# io_board.net
KiCad netlist of a schematic drawn in EAGLE
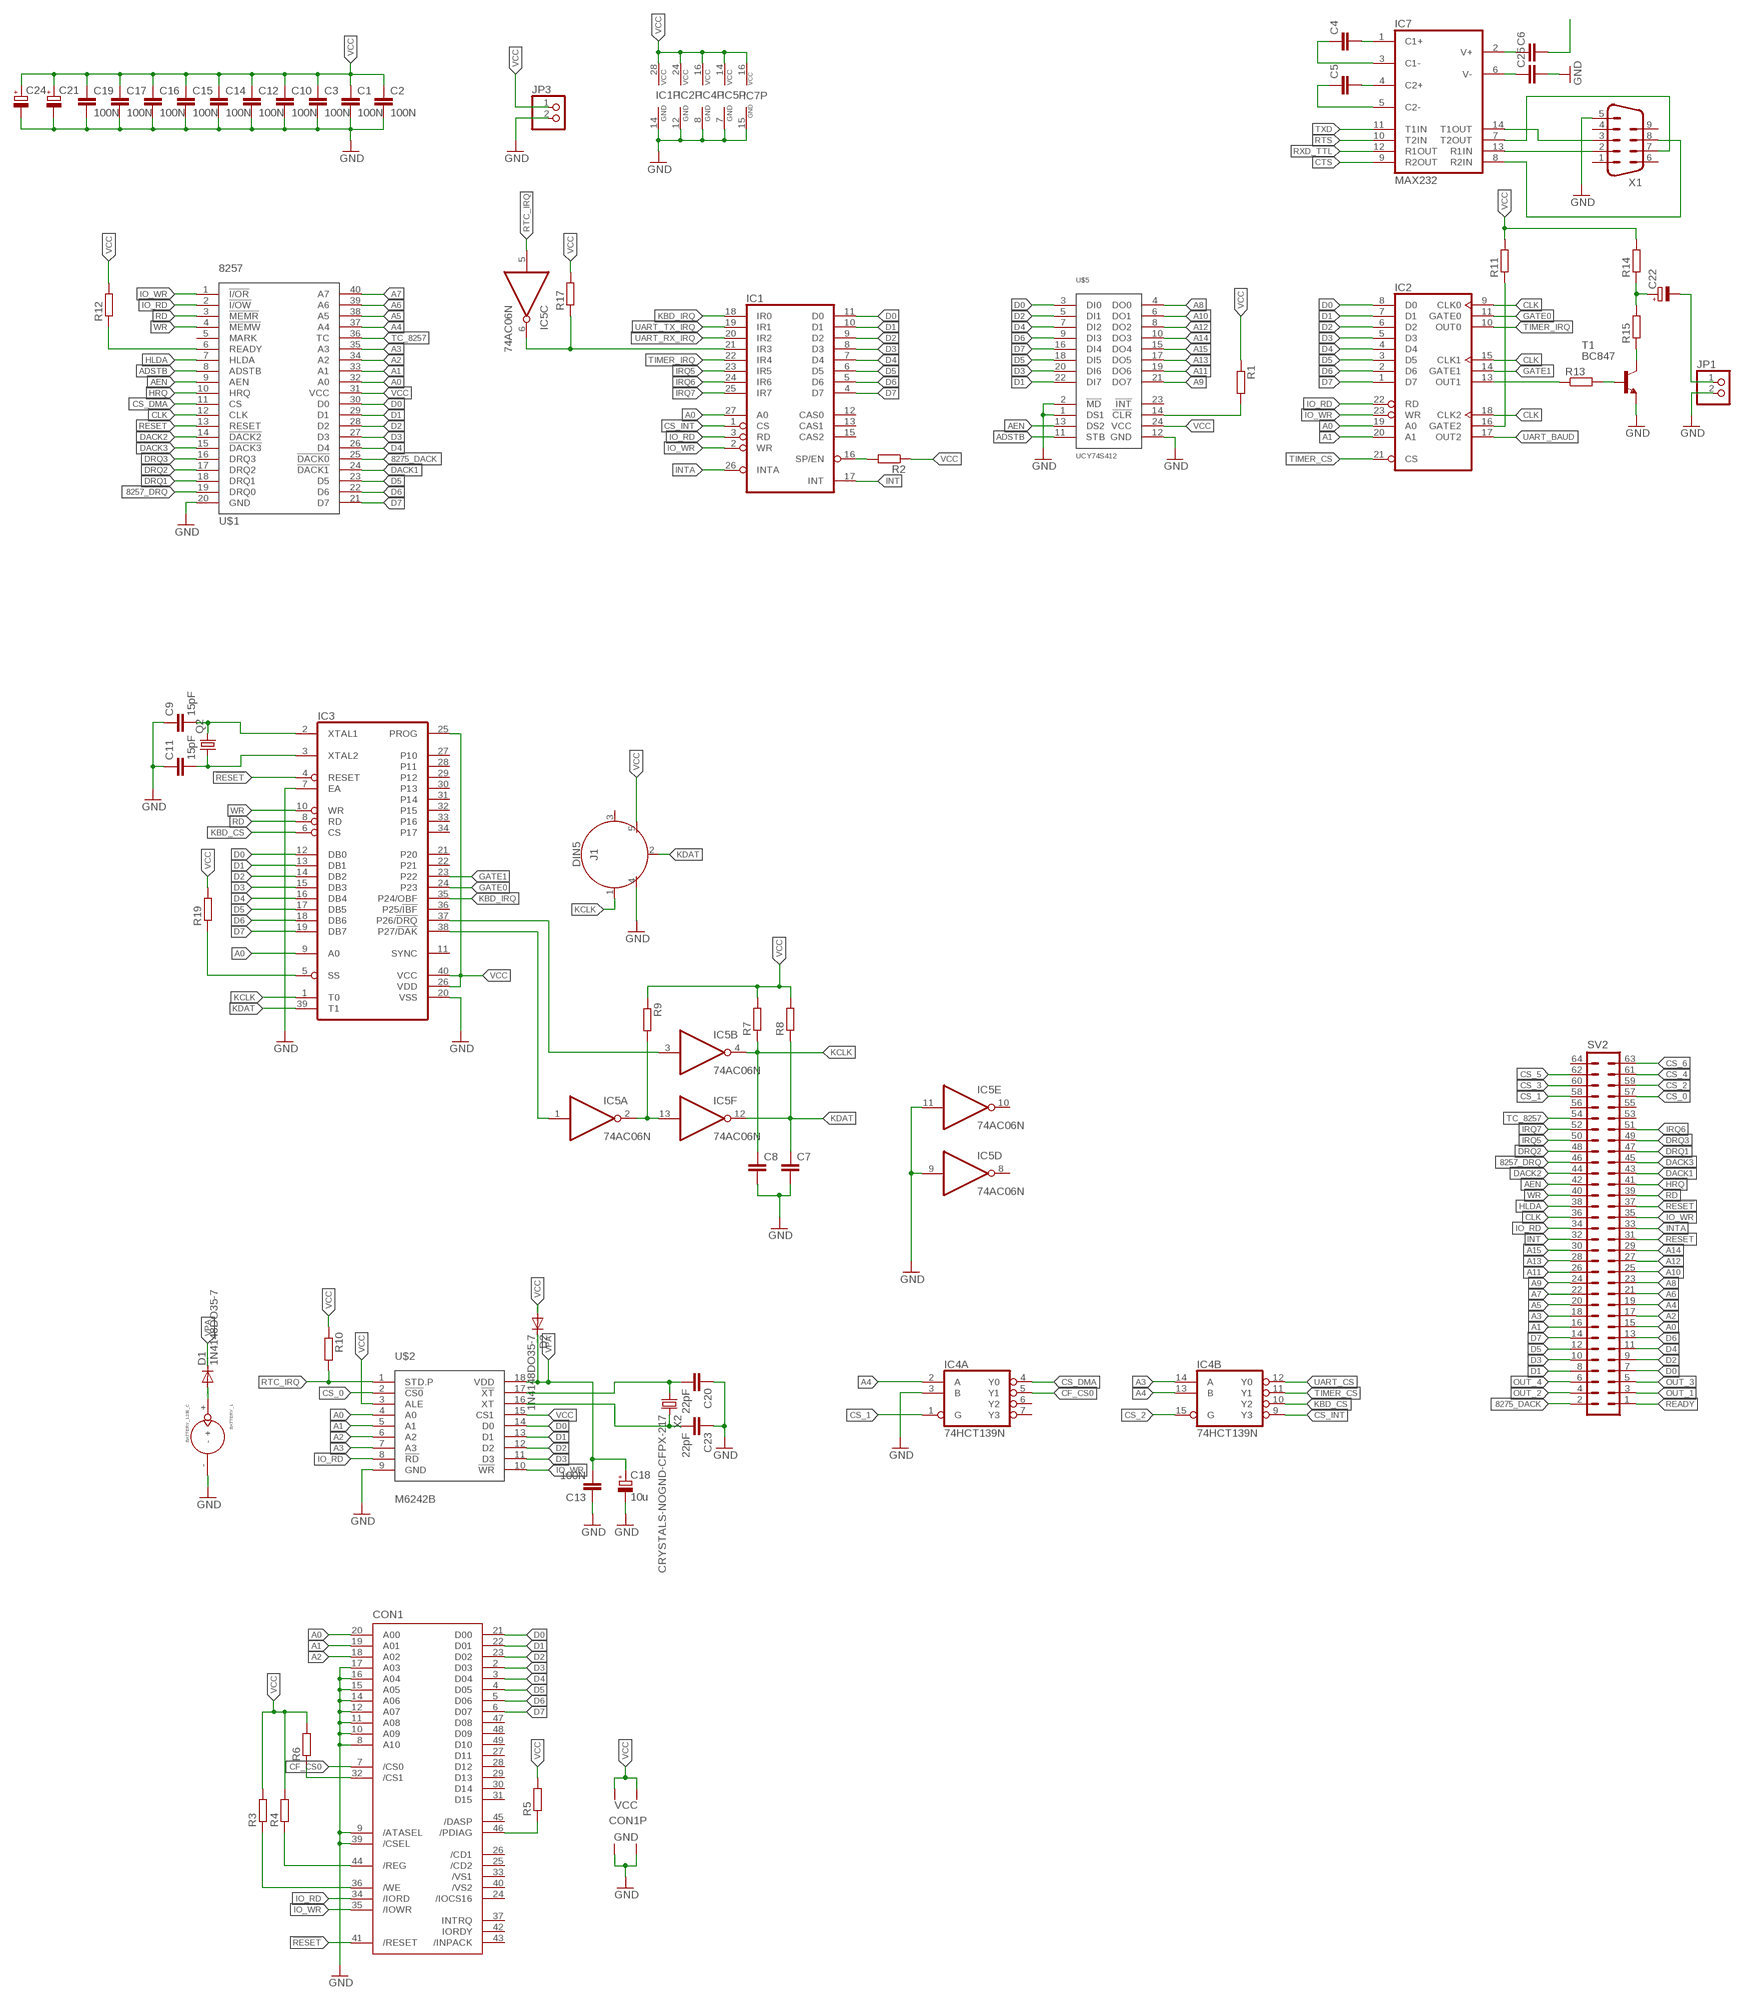
[diagram p0: schematic, sheet 1, part 1 of 2]
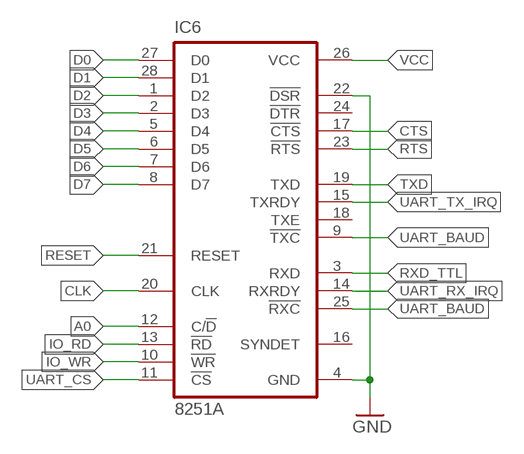
[diagram p1: schematic, sheet 1, part 2 of 2]

(export (version "E")
  (design (tool "Eeschema 10.0.6"))
  (components
    (comp (ref "BATTERY_1")
      (value "BATTERY_1236_C")
      (footprint "eagle-import:BATTERY_1236_C")
      (libsource (lib "eagle-import") (part "BATTERY_1236_C"))
    )
    (comp (ref "C1")
      (value "100N")
      (footprint "eagle-import:C0603")
      (libsource (lib "eagle-import") (part "C-EUC0603"))
    )
    (comp (ref "C2")
      (value "100N")
      (footprint "eagle-import:C1206")
      (libsource (lib "eagle-import") (part "C-EUC1206"))
    )
    (comp (ref "C3")
      (value "100N")
      (footprint "eagle-import:C0603")
      (libsource (lib "eagle-import") (part "C-EUC0603"))
    )
    (comp (ref "C4")
      (value "C-EUC0603")
      (footprint "eagle-import:C0603")
      (libsource (lib "eagle-import") (part "C-EUC0603"))
    )
    (comp (ref "C5")
      (value "C-EUC0603")
      (footprint "eagle-import:C0603")
      (libsource (lib "eagle-import") (part "C-EUC0603"))
    )
    (comp (ref "C6")
      (value "C-EUC0603")
      (footprint "eagle-import:C0603")
      (libsource (lib "eagle-import") (part "C-EUC0603"))
    )
    (comp (ref "C7")
      (value "C-EUC0603")
      (footprint "eagle-import:C0603")
      (libsource (lib "eagle-import") (part "C-EUC0603"))
    )
    (comp (ref "C8")
      (value "C-EUC0603")
      (footprint "eagle-import:C0603")
      (libsource (lib "eagle-import") (part "C-EUC0603"))
    )
    (comp (ref "C9")
      (value "15pF")
      (footprint "eagle-import:C0603")
      (libsource (lib "eagle-import") (part "C-EUC0603"))
    )
    (comp (ref "C10")
      (value "100N")
      (footprint "eagle-import:C0603")
      (libsource (lib "eagle-import") (part "C-EUC0603"))
    )
    (comp (ref "C11")
      (value "15pF")
      (footprint "eagle-import:C0603")
      (libsource (lib "eagle-import") (part "C-EUC0603"))
    )
    (comp (ref "C12")
      (value "100N")
      (footprint "eagle-import:C0603")
      (libsource (lib "eagle-import") (part "C-EUC0603"))
    )
    (comp (ref "C13")
      (value "100N")
      (footprint "eagle-import:C0603")
      (libsource (lib "eagle-import") (part "C-EUC0603"))
    )
    (comp (ref "C14")
      (value "100N")
      (footprint "eagle-import:C0603")
      (libsource (lib "eagle-import") (part "C-EUC0603"))
    )
    (comp (ref "C15")
      (value "100N")
      (footprint "eagle-import:C0603")
      (libsource (lib "eagle-import") (part "C-EUC0603"))
    )
    (comp (ref "C16")
      (value "100N")
      (footprint "eagle-import:C0603")
      (libsource (lib "eagle-import") (part "C-EUC0603"))
    )
    (comp (ref "C17")
      (value "100N")
      (footprint "eagle-import:C0603")
      (libsource (lib "eagle-import") (part "C-EUC0603"))
    )
    (comp (ref "C18")
      (value "10u")
      (footprint "eagle-import:SMC_B")
      (libsource (lib "eagle-import") (part "CPOL-EUSMCB"))
    )
    (comp (ref "C19")
      (value "100N")
      (footprint "eagle-import:C0603")
      (libsource (lib "eagle-import") (part "C-EUC0603"))
    )
    (comp (ref "C20")
      (value "22pF")
      (footprint "eagle-import:C0603")
      (libsource (lib "eagle-import") (part "C-EUC0603"))
    )
    (comp (ref "C21")
      (value "CPOL-EUE3.5-8")
      (footprint "eagle-import:E3,5-8")
      (libsource (lib "eagle-import") (part "CPOL-EUE3.5-8"))
    )
    (comp (ref "C22")
      (value "CPOL-EUE2-4")
      (footprint "eagle-import:E2-4")
      (libsource (lib "eagle-import") (part "CPOL-EUE2-4"))
    )
    (comp (ref "C23")
      (value "22pF")
      (footprint "eagle-import:C0603")
      (libsource (lib "eagle-import") (part "C-EUC0603"))
    )
    (comp (ref "C24")
      (value "CPOL-EUSMCB")
      (footprint "eagle-import:SMC_B")
      (libsource (lib "eagle-import") (part "CPOL-EUSMCB"))
    )
    (comp (ref "C25")
      (value "C-EUC0603")
      (footprint "eagle-import:C0603")
      (libsource (lib "eagle-import") (part "C-EUC0603"))
    )
    (comp (ref "CON1")
      (value "CF-CARD-IDE_MODE")
      (footprint "eagle-import:MI20-50PD-SF")
      (libsource (lib "eagle-import") (part "CF-CARD-IDE_MODE"))
    )
    (comp (ref "D1")
      (value "1N4148DO35-7")
      (footprint "eagle-import:DO35-7")
      (libsource (lib "eagle-import") (part "1N4148DO35-7"))
    )
    (comp (ref "D2")
      (value "1N4148DO35-7")
      (footprint "eagle-import:DO35-7")
      (libsource (lib "eagle-import") (part "1N4148DO35-7"))
    )
    (comp (ref "IC1")
      (value "8259A")
      (footprint "eagle-import:DIL28-6")
      (libsource (lib "eagle-import") (part "8259A"))
    )
    (comp (ref "IC2")
      (value "8253")
      (footprint "eagle-import:DIL24-6")
      (libsource (lib "eagle-import") (part "8253"))
    )
    (comp (ref "IC3")
      (value "UPI-8042AH")
      (footprint "eagle-import:DIL40")
      (libsource (lib "eagle-import") (part "UPI-8042AH"))
    )
    (comp (ref "IC4")
      (value "74HCT139N")
      (footprint "eagle-import:DIL16")
      (libsource (lib "eagle-import") (part "74139NHCT"))
    )
    (comp (ref "IC5")
      (value "74AC06N")
      (footprint "eagle-import:DIL14")
      (libsource (lib "eagle-import") (part "7406NAC"))
    )
    (comp (ref "IC6")
      (value "8251A")
      (footprint "eagle-import:DIL28-6")
      (libsource (lib "eagle-import") (part "8251A"))
    )
    (comp (ref "IC7")
      (value "MAX232")
      (footprint "eagle-import:DIL16")
      (fields (field (name "MF") "MAXIM") (field (name "MPN") "MAX232ACPE+"))
      (libsource (lib "eagle-import") (part "MAX232"))
    )
    (comp (ref "J1")
      (value "DIN5")
      (footprint "eagle-import:DIN5-RA-PTH")
      (libsource (lib "eagle-import") (part "DIN5"))
    )
    (comp (ref "JP1")
      (value "PINHD-1X2")
      (footprint "eagle-import:1X02")
      (libsource (lib "eagle-import") (part "PINHD-1X2"))
    )
    (comp (ref "JP3")
      (value "PINHD-1X2/90")
      (footprint "eagle-import:1X02_90")
      (libsource (lib "eagle-import") (part "PINHD-1X2/90"))
    )
    (comp (ref "Q2")
      (value "CRYSTALHC49S")
      (footprint "eagle-import:HC49_S")
      (libsource (lib "eagle-import") (part "CRYSTALHC49S"))
    )
    (comp (ref "R1")
      (value "R-EU_R0603")
      (footprint "eagle-import:R0603")
      (libsource (lib "eagle-import") (part "R-EU_R0603"))
    )
    (comp (ref "R2")
      (value "R-EU_R0603")
      (footprint "eagle-import:R0603")
      (libsource (lib "eagle-import") (part "R-EU_R0603"))
    )
    (comp (ref "R3")
      (value "R-EU_R0603")
      (footprint "eagle-import:R0603")
      (libsource (lib "eagle-import") (part "R-EU_R0603"))
    )
    (comp (ref "R4")
      (value "R-EU_0204/7")
      (footprint "eagle-import:0204_7")
      (libsource (lib "eagle-import") (part "R-EU_0204/7"))
    )
    (comp (ref "R5")
      (value "R-EU_R0603")
      (footprint "eagle-import:R0603")
      (libsource (lib "eagle-import") (part "R-EU_R0603"))
    )
    (comp (ref "R6")
      (value "R-EU_R0603")
      (footprint "eagle-import:R0603")
      (libsource (lib "eagle-import") (part "R-EU_R0603"))
    )
    (comp (ref "R7")
      (value "R-EU_0204/5")
      (footprint "eagle-import:0204_5")
      (libsource (lib "eagle-import") (part "R-EU_0204/5"))
    )
    (comp (ref "R8")
      (value "R-EU_M0805")
      (footprint "eagle-import:M0805")
      (libsource (lib "eagle-import") (part "R-EU_M0805"))
    )
    (comp (ref "R9")
      (value "R-EU_R0603")
      (footprint "eagle-import:R0603")
      (libsource (lib "eagle-import") (part "R-EU_R0603"))
    )
    (comp (ref "R10")
      (value "R-EU_R0603")
      (footprint "eagle-import:R0603")
      (libsource (lib "eagle-import") (part "R-EU_R0603"))
    )
    (comp (ref "R11")
      (value "R-EU_R0603")
      (footprint "eagle-import:R0603")
      (libsource (lib "eagle-import") (part "R-EU_R0603"))
    )
    (comp (ref "R12")
      (value "R-EU_R0603")
      (footprint "eagle-import:R0603")
      (libsource (lib "eagle-import") (part "R-EU_R0603"))
    )
    (comp (ref "R13")
      (value "R-EU_R0603")
      (footprint "eagle-import:R0603")
      (libsource (lib "eagle-import") (part "R-EU_R0603"))
    )
    (comp (ref "R14")
      (value "R-EU_0204/5")
      (footprint "eagle-import:0204_5")
      (libsource (lib "eagle-import") (part "R-EU_0204/5"))
    )
    (comp (ref "R15")
      (value "R-EU_R0603")
      (footprint "eagle-import:R0603")
      (libsource (lib "eagle-import") (part "R-EU_R0603"))
    )
    (comp (ref "R17")
      (value "R-EU_0204/7")
      (footprint "eagle-import:0204_7")
      (libsource (lib "eagle-import") (part "R-EU_0204/7"))
    )
    (comp (ref "R19")
      (value "R-EU_0204/5")
      (footprint "eagle-import:0204_5")
      (libsource (lib "eagle-import") (part "R-EU_0204/5"))
    )
    (comp (ref "SV2")
      (value "ML64L")
      (footprint "eagle-import:ML64L")
      (libsource (lib "eagle-import") (part "ML64L"))
    )
    (comp (ref "T1")
      (value "BC847")
      (footprint "eagle-import:SOT23")
      (libsource (lib "eagle-import") (part "BC847"))
    )
    (comp (ref "U$1")
      (value "8257")
      (footprint "eagle-import:DIL40")
      (libsource (lib "eagle-import") (part "8257"))
    )
    (comp (ref "U$2")
      (value "M6242B")
      (footprint "eagle-import:DIL18")
      (libsource (lib "eagle-import") (part "M6242B"))
    )
    (comp (ref "U$5")
      (value "UCY74S412")
      (footprint "eagle-import:DIL24-6")
      (libsource (lib "eagle-import") (part "UCY74S412"))
    )
    (comp (ref "X1")
      (value "M09HP")
      (footprint "eagle-import:M09HP")
      (libsource (lib "eagle-import") (part "M09HP"))
    )
    (comp (ref "X2")
      (value "CRYSTALS-NOGND-CFPX-217")
      (footprint "eagle-import:3.2X1.5-2-PAD")
      (libsource (lib "eagle-import") (part "CRYSTALS-NOGND-CFPX-217"))
    )
  )
  (nets
    (net (code "1") (name "/~{RESET}") (class "Default")
      (node (ref "CON1") (pin "41") (pinfunction "/RESET_41") (pintype "input"))
      (node (ref "IC3") (pin "4") (pinfunction "RESET_4") (pintype "input"))
      (node (ref "SV2") (pin "37") (pinfunction "37_37") (pintype "passive"))
    )
    (net (code "2") (name "8257_DRQ") (class "Default")
      (node (ref "SV2") (pin "46") (pinfunction "46_46") (pintype "passive"))
      (node (ref "U$1") (pin "19") (pinfunction "DRQ0_19") (pintype "bidirectional"))
    )
    (net (code "3") (name "8275_DACK") (class "Default")
      (node (ref "SV2") (pin "2") (pinfunction "2_2") (pintype "passive"))
      (node (ref "U$1") (pin "25") (pinfunction "~{DACK0}_25") (pintype "bidirectional"))
    )
    (net (code "4") (name "A0") (class "Default")
      (node (ref "CON1") (pin "20") (pinfunction "A00_20") (pintype "input"))
      (node (ref "IC1") (pin "27") (pinfunction "A0_27") (pintype "input"))
      (node (ref "IC2") (pin "19") (pinfunction "A0_19") (pintype "input"))
      (node (ref "IC3") (pin "9") (pinfunction "A0_9") (pintype "input"))
      (node (ref "IC6") (pin "12") (pinfunction "C/~{D}_12") (pintype "input"))
      (node (ref "SV2") (pin "15") (pinfunction "15_15") (pintype "passive"))
      (node (ref "U$1") (pin "32") (pinfunction "A0_32") (pintype "bidirectional"))
      (node (ref "U$2") (pin "4") (pinfunction "A0_4") (pintype "bidirectional"))
    )
    (net (code "5") (name "A1") (class "Default")
      (node (ref "CON1") (pin "19") (pinfunction "A01_19") (pintype "input"))
      (node (ref "IC2") (pin "20") (pinfunction "A1_20") (pintype "input"))
      (node (ref "SV2") (pin "16") (pinfunction "16_16") (pintype "passive"))
      (node (ref "U$1") (pin "33") (pinfunction "A1_33") (pintype "bidirectional"))
      (node (ref "U$2") (pin "5") (pinfunction "A1_5") (pintype "bidirectional"))
    )
    (net (code "6") (name "A2") (class "Default")
      (node (ref "CON1") (pin "18") (pinfunction "A02_18") (pintype "input"))
      (node (ref "SV2") (pin "17") (pinfunction "17_17") (pintype "passive"))
      (node (ref "U$1") (pin "34") (pinfunction "A2_34") (pintype "bidirectional"))
      (node (ref "U$2") (pin "6") (pinfunction "A2_6") (pintype "bidirectional"))
    )
    (net (code "7") (name "A3") (class "Default")
      (node (ref "IC4") (pin "14") (pinfunction "A_14") (pintype "input"))
      (node (ref "SV2") (pin "18") (pinfunction "18_18") (pintype "passive"))
      (node (ref "U$1") (pin "35") (pinfunction "A3_35") (pintype "bidirectional"))
      (node (ref "U$2") (pin "7") (pinfunction "A3_7") (pintype "bidirectional"))
    )
    (net (code "8") (name "A4") (class "Default")
      (node (ref "IC4") (pin "13") (pinfunction "B_13") (pintype "input"))
      (node (ref "IC4") (pin "2") (pinfunction "A_2") (pintype "input"))
      (node (ref "SV2") (pin "19") (pinfunction "19_19") (pintype "passive"))
      (node (ref "U$1") (pin "37") (pinfunction "A4_37") (pintype "bidirectional"))
    )
    (net (code "9") (name "A5") (class "Default")
      (node (ref "SV2") (pin "20") (pinfunction "20_20") (pintype "passive"))
      (node (ref "U$1") (pin "38") (pinfunction "A5_38") (pintype "bidirectional"))
    )
    (net (code "10") (name "A6") (class "Default")
      (node (ref "SV2") (pin "21") (pinfunction "21_21") (pintype "passive"))
      (node (ref "U$1") (pin "39") (pinfunction "A6_39") (pintype "bidirectional"))
    )
    (net (code "11") (name "A7") (class "Default")
      (node (ref "SV2") (pin "22") (pinfunction "22_22") (pintype "passive"))
      (node (ref "U$1") (pin "40") (pinfunction "A7_40") (pintype "bidirectional"))
    )
    (net (code "12") (name "A8") (class "Default")
      (node (ref "SV2") (pin "23") (pinfunction "23_23") (pintype "passive"))
      (node (ref "U$5") (pin "4") (pinfunction "DO0_4") (pintype "bidirectional"))
    )
    (net (code "13") (name "A9") (class "Default")
      (node (ref "SV2") (pin "24") (pinfunction "24_24") (pintype "passive"))
      (node (ref "U$5") (pin "21") (pinfunction "DO7_21") (pintype "bidirectional"))
    )
    (net (code "14") (name "A10") (class "Default")
      (node (ref "SV2") (pin "25") (pinfunction "25_25") (pintype "passive"))
      (node (ref "U$5") (pin "6") (pinfunction "DO1_6") (pintype "bidirectional"))
    )
    (net (code "15") (name "A11") (class "Default")
      (node (ref "SV2") (pin "26") (pinfunction "26_26") (pintype "passive"))
      (node (ref "U$5") (pin "19") (pinfunction "DO6_19") (pintype "bidirectional"))
    )
    (net (code "16") (name "A12") (class "Default")
      (node (ref "SV2") (pin "27") (pinfunction "27_27") (pintype "passive"))
      (node (ref "U$5") (pin "8") (pinfunction "DO2_8") (pintype "bidirectional"))
    )
    (net (code "17") (name "A13") (class "Default")
      (node (ref "SV2") (pin "28") (pinfunction "28_28") (pintype "passive"))
      (node (ref "U$5") (pin "17") (pinfunction "DO5_17") (pintype "bidirectional"))
    )
    (net (code "18") (name "A14") (class "Default")
      (node (ref "SV2") (pin "29") (pinfunction "29_29") (pintype "passive"))
      (node (ref "U$5") (pin "10") (pinfunction "DO3_10") (pintype "bidirectional"))
    )
    (net (code "19") (name "A15") (class "Default")
      (node (ref "SV2") (pin "30") (pinfunction "30_30") (pintype "passive"))
      (node (ref "U$5") (pin "15") (pinfunction "DO4_15") (pintype "bidirectional"))
    )
    (net (code "20") (name "ADSTB") (class "Default")
      (node (ref "U$1") (pin "8") (pinfunction "ADSTB_8") (pintype "bidirectional"))
      (node (ref "U$5") (pin "11") (pinfunction "STB_11") (pintype "bidirectional"))
    )
    (net (code "21") (name "AEN") (class "Default")
      (node (ref "SV2") (pin "42") (pinfunction "42_42") (pintype "passive"))
      (node (ref "U$1") (pin "9") (pinfunction "AEN_9") (pintype "bidirectional"))
      (node (ref "U$5") (pin "13") (pinfunction "DS2_13") (pintype "bidirectional"))
    )
    (net (code "22") (name "CF_CS0") (class "Default")
      (node (ref "CON1") (pin "7") (pinfunction "/CS0_7") (pintype "input"))
      (node (ref "IC4") (pin "5") (pinfunction "Y1_5") (pintype "output"))
    )
    (net (code "23") (name "CLK") (class "Default")
      (node (ref "IC2") (pin "15") (pinfunction "CLK1_15") (pintype "input"))
      (node (ref "IC2") (pin "18") (pinfunction "CLK2_18") (pintype "input"))
      (node (ref "IC2") (pin "9") (pinfunction "CLK0_9") (pintype "input"))
      (node (ref "IC6") (pin "20") (pinfunction "CLK_20") (pintype "input"))
      (node (ref "SV2") (pin "36") (pinfunction "36_36") (pintype "passive"))
      (node (ref "U$1") (pin "12") (pinfunction "CLK_12") (pintype "bidirectional"))
    )
    (net (code "24") (name "CS_0") (class "Default")
      (node (ref "SV2") (pin "57") (pinfunction "57_57") (pintype "passive"))
      (node (ref "U$2") (pin "2") (pinfunction "~{CS0}_2") (pintype "bidirectional"))
    )
    (net (code "25") (name "CS_1") (class "Default")
      (node (ref "IC4") (pin "1") (pinfunction "G_1") (pintype "input"))
      (node (ref "SV2") (pin "58") (pinfunction "58_58") (pintype "passive"))
    )
    (net (code "26") (name "CS_2") (class "Default")
      (node (ref "IC4") (pin "15") (pinfunction "G_15") (pintype "input"))
      (node (ref "SV2") (pin "59") (pinfunction "59_59") (pintype "passive"))
    )
    (net (code "27") (name "CS_3") (class "Default")
      (node (ref "SV2") (pin "60") (pinfunction "60_60") (pintype "passive"))
    )
    (net (code "28") (name "CS_4") (class "Default")
      (node (ref "SV2") (pin "61") (pinfunction "61_61") (pintype "passive"))
    )
    (net (code "29") (name "CS_5") (class "Default")
      (node (ref "SV2") (pin "62") (pinfunction "62_62") (pintype "passive"))
    )
    (net (code "30") (name "CS_6") (class "Default")
      (node (ref "SV2") (pin "63") (pinfunction "63_63") (pintype "passive"))
    )
    (net (code "31") (name "CS_DMA") (class "Default")
      (node (ref "IC4") (pin "4") (pinfunction "Y0_4") (pintype "output"))
      (node (ref "U$1") (pin "11") (pinfunction "CS_11") (pintype "bidirectional"))
    )
    (net (code "32") (name "CS_INT") (class "Default")
      (node (ref "IC1") (pin "1") (pinfunction "CS_1") (pintype "input"))
      (node (ref "IC4") (pin "9") (pinfunction "Y3_9") (pintype "output"))
    )
    (net (code "33") (name "CTS") (class "Default")
      (node (ref "IC6") (pin "17") (pinfunction "~{CTS}_17") (pintype "input"))
      (node (ref "IC7") (pin "9") (pinfunction "R2OUT_9") (pintype "output"))
    )
    (net (code "34") (name "D0") (class "Default")
      (node (ref "CON1") (pin "21") (pinfunction "D00_21") (pintype "bidirectional"))
      (node (ref "IC1") (pin "11") (pinfunction "D0_11") (pintype "bidirectional"))
      (node (ref "IC2") (pin "8") (pinfunction "D0_8") (pintype "bidirectional"))
      (node (ref "IC3") (pin "12") (pinfunction "DB0_12") (pintype "bidirectional"))
      (node (ref "IC6") (pin "27") (pinfunction "D0_27") (pintype "tri_state"))
      (node (ref "SV2") (pin "7") (pinfunction "7_7") (pintype "passive"))
      (node (ref "U$1") (pin "30") (pinfunction "D0_30") (pintype "bidirectional"))
      (node (ref "U$2") (pin "14") (pinfunction "D0_14") (pintype "bidirectional"))
      (node (ref "U$5") (pin "3") (pinfunction "DI0_3") (pintype "bidirectional"))
    )
    (net (code "35") (name "D1") (class "Default")
      (node (ref "CON1") (pin "22") (pinfunction "D01_22") (pintype "bidirectional"))
      (node (ref "IC1") (pin "10") (pinfunction "D1_10") (pintype "bidirectional"))
      (node (ref "IC2") (pin "7") (pinfunction "D1_7") (pintype "bidirectional"))
      (node (ref "IC3") (pin "13") (pinfunction "DB1_13") (pintype "bidirectional"))
      (node (ref "IC6") (pin "28") (pinfunction "D1_28") (pintype "tri_state"))
      (node (ref "SV2") (pin "8") (pinfunction "8_8") (pintype "passive"))
      (node (ref "U$1") (pin "29") (pinfunction "D1_29") (pintype "bidirectional"))
      (node (ref "U$2") (pin "13") (pinfunction "D1_13") (pintype "bidirectional"))
      (node (ref "U$5") (pin "22") (pinfunction "DI7_22") (pintype "bidirectional"))
    )
    (net (code "36") (name "D2") (class "Default")
      (node (ref "CON1") (pin "23") (pinfunction "D02_23") (pintype "bidirectional"))
      (node (ref "IC1") (pin "9") (pinfunction "D2_9") (pintype "bidirectional"))
      (node (ref "IC2") (pin "6") (pinfunction "D2_6") (pintype "bidirectional"))
      (node (ref "IC3") (pin "14") (pinfunction "DB2_14") (pintype "bidirectional"))
      (node (ref "IC6") (pin "1") (pinfunction "D2_1") (pintype "tri_state"))
      (node (ref "SV2") (pin "9") (pinfunction "9_9") (pintype "passive"))
      (node (ref "U$1") (pin "28") (pinfunction "D2_28") (pintype "bidirectional"))
      (node (ref "U$2") (pin "12") (pinfunction "D2_12") (pintype "bidirectional"))
      (node (ref "U$5") (pin "5") (pinfunction "DI1_5") (pintype "bidirectional"))
    )
    (net (code "37") (name "D3") (class "Default")
      (node (ref "CON1") (pin "2") (pinfunction "D03_2") (pintype "bidirectional"))
      (node (ref "IC1") (pin "8") (pinfunction "D3_8") (pintype "bidirectional"))
      (node (ref "IC2") (pin "5") (pinfunction "D3_5") (pintype "bidirectional"))
      (node (ref "IC3") (pin "15") (pinfunction "DB3_15") (pintype "bidirectional"))
      (node (ref "IC6") (pin "2") (pinfunction "D3_2") (pintype "tri_state"))
      (node (ref "SV2") (pin "10") (pinfunction "10_10") (pintype "passive"))
      (node (ref "U$1") (pin "27") (pinfunction "D3_27") (pintype "bidirectional"))
      (node (ref "U$2") (pin "11") (pinfunction "D3_11") (pintype "bidirectional"))
      (node (ref "U$5") (pin "20") (pinfunction "DI6_20") (pintype "bidirectional"))
    )
    (net (code "38") (name "D4") (class "Default")
      (node (ref "CON1") (pin "3") (pinfunction "D04_3") (pintype "bidirectional"))
      (node (ref "IC1") (pin "7") (pinfunction "D4_7") (pintype "bidirectional"))
      (node (ref "IC2") (pin "4") (pinfunction "D4_4") (pintype "bidirectional"))
      (node (ref "IC3") (pin "16") (pinfunction "DB4_16") (pintype "bidirectional"))
      (node (ref "IC6") (pin "5") (pinfunction "D4_5") (pintype "tri_state"))
      (node (ref "SV2") (pin "11") (pinfunction "11_11") (pintype "passive"))
      (node (ref "U$1") (pin "26") (pinfunction "D4_26") (pintype "bidirectional"))
      (node (ref "U$5") (pin "7") (pinfunction "DI2_7") (pintype "bidirectional"))
    )
    (net (code "39") (name "D5") (class "Default")
      (node (ref "CON1") (pin "4") (pinfunction "D05_4") (pintype "bidirectional"))
      (node (ref "IC1") (pin "6") (pinfunction "D5_6") (pintype "bidirectional"))
      (node (ref "IC2") (pin "3") (pinfunction "D5_3") (pintype "bidirectional"))
      (node (ref "IC3") (pin "17") (pinfunction "DB5_17") (pintype "bidirectional"))
      (node (ref "IC6") (pin "6") (pinfunction "D5_6") (pintype "tri_state"))
      (node (ref "SV2") (pin "12") (pinfunction "12_12") (pintype "passive"))
      (node (ref "U$1") (pin "23") (pinfunction "D5_23") (pintype "bidirectional"))
      (node (ref "U$5") (pin "18") (pinfunction "DI5_18") (pintype "bidirectional"))
    )
    (net (code "40") (name "D6") (class "Default")
      (node (ref "CON1") (pin "5") (pinfunction "D06_5") (pintype "bidirectional"))
      (node (ref "IC1") (pin "5") (pinfunction "D6_5") (pintype "bidirectional"))
      (node (ref "IC2") (pin "2") (pinfunction "D6_2") (pintype "bidirectional"))
      (node (ref "IC3") (pin "18") (pinfunction "DB6_18") (pintype "bidirectional"))
      (node (ref "IC6") (pin "7") (pinfunction "D6_7") (pintype "tri_state"))
      (node (ref "SV2") (pin "13") (pinfunction "13_13") (pintype "passive"))
      (node (ref "U$1") (pin "22") (pinfunction "D6_22") (pintype "bidirectional"))
      (node (ref "U$5") (pin "9") (pinfunction "DI3_9") (pintype "bidirectional"))
    )
    (net (code "41") (name "D7") (class "Default")
      (node (ref "CON1") (pin "6") (pinfunction "D07_6") (pintype "bidirectional"))
      (node (ref "IC1") (pin "4") (pinfunction "D7_4") (pintype "bidirectional"))
      (node (ref "IC2") (pin "1") (pinfunction "D7_1") (pintype "bidirectional"))
      (node (ref "IC3") (pin "19") (pinfunction "DB7_19") (pintype "bidirectional"))
      (node (ref "IC6") (pin "8") (pinfunction "D7_8") (pintype "tri_state"))
      (node (ref "SV2") (pin "14") (pinfunction "14_14") (pintype "passive"))
      (node (ref "U$1") (pin "21") (pinfunction "D7_21") (pintype "bidirectional"))
      (node (ref "U$5") (pin "16") (pinfunction "DI4_16") (pintype "bidirectional"))
    )
    (net (code "42") (name "DACK1") (class "Default")
      (node (ref "SV2") (pin "43") (pinfunction "43_43") (pintype "passive"))
      (node (ref "U$1") (pin "24") (pinfunction "~{DACK1}_24") (pintype "bidirectional"))
    )
    (net (code "43") (name "DACK2") (class "Default")
      (node (ref "SV2") (pin "44") (pinfunction "44_44") (pintype "passive"))
      (node (ref "U$1") (pin "14") (pinfunction "~{DACK2}_14") (pintype "bidirectional"))
    )
    (net (code "44") (name "DACK3") (class "Default")
      (node (ref "SV2") (pin "45") (pinfunction "45_45") (pintype "passive"))
      (node (ref "U$1") (pin "15") (pinfunction "~{DACK3}_15") (pintype "bidirectional"))
    )
    (net (code "45") (name "DRQ1") (class "Default")
      (node (ref "SV2") (pin "47") (pinfunction "47_47") (pintype "passive"))
      (node (ref "U$1") (pin "18") (pinfunction "DRQ1_18") (pintype "bidirectional"))
    )
    (net (code "46") (name "DRQ2") (class "Default")
      (node (ref "SV2") (pin "48") (pinfunction "48_48") (pintype "passive"))
      (node (ref "U$1") (pin "17") (pinfunction "DRQ2_17") (pintype "bidirectional"))
    )
    (net (code "47") (name "DRQ3") (class "Default")
      (node (ref "SV2") (pin "49") (pinfunction "49_49") (pintype "passive"))
      (node (ref "U$1") (pin "16") (pinfunction "DRQ3_16") (pintype "bidirectional"))
    )
    (net (code "48") (name "GATE0") (class "Default")
      (node (ref "IC2") (pin "11") (pinfunction "GATE0_11") (pintype "input"))
      (node (ref "IC3") (pin "24") (pinfunction "P23_24") (pintype "bidirectional"))
    )
    (net (code "49") (name "GATE1") (class "Default")
      (node (ref "IC2") (pin "14") (pinfunction "GATE1_14") (pintype "input"))
      (node (ref "IC3") (pin "23") (pinfunction "P22_23") (pintype "bidirectional"))
    )
    (net (code "50") (name "GND") (class "Default")
      (node (ref "BATTERY_1") (pin "-") (pinfunction "-_-") (pintype "bidirectional"))
      (node (ref "C1") (pin "2") (pinfunction "2_2") (pintype "passive"))
      (node (ref "C10") (pin "2") (pinfunction "2_2") (pintype "passive"))
      (node (ref "C11") (pin "1") (pinfunction "1_1") (pintype "passive"))
      (node (ref "C12") (pin "2") (pinfunction "2_2") (pintype "passive"))
      (node (ref "C13") (pin "1") (pinfunction "1_1") (pintype "passive"))
      (node (ref "C14") (pin "2") (pinfunction "2_2") (pintype "passive"))
      (node (ref "C15") (pin "2") (pinfunction "2_2") (pintype "passive"))
      (node (ref "C16") (pin "2") (pinfunction "2_2") (pintype "passive"))
      (node (ref "C17") (pin "2") (pinfunction "2_2") (pintype "passive"))
      (node (ref "C18") (pin "-") (pinfunction "-_-") (pintype "passive"))
      (node (ref "C19") (pin "2") (pinfunction "2_2") (pintype "passive"))
      (node (ref "C2") (pin "2") (pinfunction "2_2") (pintype "passive"))
      (node (ref "C20") (pin "1") (pinfunction "1_1") (pintype "passive"))
      (node (ref "C21") (pin "-") (pinfunction "-_-") (pintype "passive"))
      (node (ref "C23") (pin "1") (pinfunction "1_1") (pintype "passive"))
      (node (ref "C24") (pin "-") (pinfunction "-_-") (pintype "passive"))
      (node (ref "C25") (pin "2") (pinfunction "2_2") (pintype "passive"))
      (node (ref "C3") (pin "2") (pinfunction "2_2") (pintype "passive"))
      (node (ref "C7") (pin "2") (pinfunction "2_2") (pintype "passive"))
      (node (ref "C8") (pin "2") (pinfunction "2_2") (pintype "passive"))
      (node (ref "C9") (pin "1") (pinfunction "1_1") (pintype "passive"))
      (node (ref "CON1") (pin "1") (pinfunction "GND1_1") (pintype "power_in"))
      (node (ref "CON1") (pin "10") (pinfunction "A09_10") (pintype "input"))
      (node (ref "CON1") (pin "11") (pinfunction "A08_11") (pintype "input"))
      (node (ref "CON1") (pin "12") (pinfunction "A07_12") (pintype "input"))
      (node (ref "CON1") (pin "14") (pinfunction "A06_14") (pintype "input"))
      (node (ref "CON1") (pin "15") (pinfunction "A05_15") (pintype "input"))
      (node (ref "CON1") (pin "16") (pinfunction "A04_16") (pintype "input"))
      (node (ref "CON1") (pin "17") (pinfunction "A03_17") (pintype "input"))
      (node (ref "CON1") (pin "39") (pinfunction "/CSEL_39") (pintype "input"))
      (node (ref "CON1") (pin "50") (pinfunction "GND2_50") (pintype "power_in"))
      (node (ref "CON1") (pin "8") (pinfunction "A10_8") (pintype "input"))
      (node (ref "CON1") (pin "9") (pinfunction "/ATASEL_9") (pintype "input"))
      (node (ref "IC1") (pin "14") (pinfunction "GND_14") (pintype "power_in"))
      (node (ref "IC2") (pin "12") (pinfunction "GND_12") (pintype "power_in"))
      (node (ref "IC3") (pin "20") (pinfunction "VSS_20") (pintype "power_in"))
      (node (ref "IC3") (pin "7") (pinfunction "EA_7") (pintype "input"))
      (node (ref "IC4") (pin "3") (pinfunction "B_3") (pintype "input"))
      (node (ref "IC4") (pin "8") (pinfunction "GND_8") (pintype "power_in"))
      (node (ref "IC5") (pin "11") (pinfunction "I_11") (pintype "input"))
      (node (ref "IC5") (pin "7") (pinfunction "GND_7") (pintype "power_in"))
      (node (ref "IC5") (pin "9") (pinfunction "I_9") (pintype "input"))
      (node (ref "IC6") (pin "22") (pinfunction "~{DSR}_22") (pintype "input"))
      (node (ref "IC6") (pin "4") (pinfunction "GND_4") (pintype "power_in"))
      (node (ref "IC7") (pin "15") (pinfunction "GND_15") (pintype "power_in"))
      (node (ref "J1") (pin "4") (pinfunction "4_4") (pintype "bidirectional"))
      (node (ref "JP1") (pin "2") (pinfunction "2_2") (pintype "passive"))
      (node (ref "JP3") (pin "2") (pinfunction "2_2") (pintype "passive"))
      (node (ref "T1") (pin "2") (pinfunction "E_2") (pintype "passive"))
      (node (ref "U$1") (pin "20") (pinfunction "GND_20") (pintype "bidirectional"))
      (node (ref "U$2") (pin "9") (pinfunction "GND_9") (pintype "bidirectional"))
      (node (ref "U$5") (pin "1") (pinfunction "DS1_1") (pintype "bidirectional"))
      (node (ref "U$5") (pin "12") (pinfunction "GND_12") (pintype "bidirectional"))
      (node (ref "U$5") (pin "2") (pinfunction "~{MD}_2") (pintype "bidirectional"))
      (node (ref "X1") (pin "5") (pinfunction "5_5") (pintype "passive"))
    )
    (net (code "51") (name "HLDA") (class "Default")
      (node (ref "SV2") (pin "38") (pinfunction "38_38") (pintype "passive"))
      (node (ref "U$1") (pin "7") (pinfunction "HLDA_7") (pintype "bidirectional"))
    )
    (net (code "52") (name "HRQ") (class "Default")
      (node (ref "SV2") (pin "41") (pinfunction "41_41") (pintype "passive"))
      (node (ref "U$1") (pin "10") (pinfunction "HRQ_10") (pintype "bidirectional"))
    )
    (net (code "53") (name "INT") (class "Default")
      (node (ref "IC1") (pin "17") (pinfunction "INT_17") (pintype "output"))
      (node (ref "SV2") (pin "32") (pinfunction "32_32") (pintype "passive"))
    )
    (net (code "54") (name "INTA") (class "Default")
      (node (ref "IC1") (pin "26") (pinfunction "INTA_26") (pintype "input"))
      (node (ref "SV2") (pin "33") (pinfunction "33_33") (pintype "passive"))
    )
    (net (code "55") (name "IO_RD") (class "Default")
      (node (ref "CON1") (pin "34") (pinfunction "/IORD_34") (pintype "input"))
      (node (ref "IC1") (pin "3") (pinfunction "RD_3") (pintype "input"))
      (node (ref "IC2") (pin "22") (pinfunction "RD_22") (pintype "input"))
      (node (ref "IC6") (pin "13") (pinfunction "~{RD}_13") (pintype "input"))
      (node (ref "SV2") (pin "34") (pinfunction "34_34") (pintype "passive"))
      (node (ref "U$1") (pin "2") (pinfunction "~{I/OW}_2") (pintype "bidirectional"))
      (node (ref "U$2") (pin "8") (pinfunction "~{RD}_8") (pintype "bidirectional"))
    )
    (net (code "56") (name "IO_WR") (class "Default")
      (node (ref "CON1") (pin "35") (pinfunction "/IOWR_35") (pintype "input"))
      (node (ref "IC1") (pin "2") (pinfunction "WR_2") (pintype "input"))
      (node (ref "IC2") (pin "23") (pinfunction "WR_23") (pintype "input"))
      (node (ref "IC6") (pin "10") (pinfunction "~{WR}_10") (pintype "input"))
      (node (ref "SV2") (pin "35") (pinfunction "35_35") (pintype "passive"))
      (node (ref "U$1") (pin "1") (pinfunction "~{I/OR}_1") (pintype "bidirectional"))
      (node (ref "U$2") (pin "10") (pinfunction "~{WR}_10") (pintype "bidirectional"))
    )
    (net (code "57") (name "IRQ5") (class "Default")
      (node (ref "IC1") (pin "23") (pinfunction "IR5_23") (pintype "input"))
      (node (ref "SV2") (pin "50") (pinfunction "50_50") (pintype "passive"))
    )
    (net (code "58") (name "IRQ6") (class "Default")
      (node (ref "IC1") (pin "24") (pinfunction "IR6_24") (pintype "input"))
      (node (ref "SV2") (pin "51") (pinfunction "51_51") (pintype "passive"))
    )
    (net (code "59") (name "IRQ7") (class "Default")
      (node (ref "IC1") (pin "25") (pinfunction "IR7_25") (pintype "input"))
      (node (ref "SV2") (pin "52") (pinfunction "52_52") (pintype "passive"))
    )
    (net (code "60") (name "KBD_CS") (class "Default")
      (node (ref "IC3") (pin "6") (pinfunction "CS_6") (pintype "input"))
      (node (ref "IC4") (pin "10") (pinfunction "Y2_10") (pintype "output"))
    )
    (net (code "61") (name "KBD_IRQ") (class "Default")
      (node (ref "IC1") (pin "18") (pinfunction "IR0_18") (pintype "input"))
      (node (ref "IC3") (pin "35") (pinfunction "P24/OBF_35") (pintype "bidirectional"))
    )
    (net (code "62") (name "KCLK") (class "Default")
      (node (ref "C8") (pin "1") (pinfunction "1_1") (pintype "passive"))
      (node (ref "IC3") (pin "1") (pinfunction "T0_1") (pintype "input"))
      (node (ref "IC5") (pin "4") (pinfunction "O_4") (pintype "open_collector"))
      (node (ref "J1") (pin "1") (pinfunction "1_1") (pintype "bidirectional"))
      (node (ref "R7") (pin "1") (pinfunction "1_1") (pintype "passive"))
    )
    (net (code "63") (name "KDAT") (class "Default")
      (node (ref "C7") (pin "1") (pinfunction "1_1") (pintype "passive"))
      (node (ref "IC3") (pin "39") (pinfunction "T1_39") (pintype "input"))
      (node (ref "IC5") (pin "12") (pinfunction "O_12") (pintype "open_collector"))
      (node (ref "J1") (pin "2") (pinfunction "2_2") (pintype "bidirectional"))
      (node (ref "R8") (pin "1") (pinfunction "1_1") (pintype "passive"))
    )
    (net (code "64") (name "Net-(BATTERY_1-Pad+)") (class "Default")
      (node (ref "BATTERY_1") (pin "+") (pinfunction "+_+") (pintype "bidirectional"))
      (node (ref "D1") (pin "A") (pinfunction "A_A") (pintype "passive"))
    )
    (net (code "65") (name "Net-(C22-Pad+)") (class "Default")
      (node (ref "C22") (pin "+") (pinfunction "+_+") (pintype "passive"))
      (node (ref "R14") (pin "1") (pinfunction "1_1") (pintype "passive"))
      (node (ref "R15") (pin "2") (pinfunction "2_2") (pintype "passive"))
    )
    (net (code "66") (name "Net-(C22-Pad-)") (class "Default")
      (node (ref "C22") (pin "-") (pinfunction "-_-") (pintype "passive"))
      (node (ref "JP1") (pin "1") (pinfunction "1_1") (pintype "passive"))
    )
    (net (code "67") (name "Net-(CON1A-{slash}CS1)") (class "Default")
      (node (ref "CON1") (pin "32") (pinfunction "/CS1_32") (pintype "input"))
      (node (ref "R6") (pin "1") (pinfunction "1_1") (pintype "passive"))
    )
    (net (code "68") (name "Net-(CON1A-{slash}PDIAG)") (class "Default")
      (node (ref "CON1") (pin "46") (pinfunction "/PDIAG_46") (pintype "bidirectional"))
      (node (ref "R5") (pin "1") (pinfunction "1_1") (pintype "passive"))
    )
    (net (code "69") (name "Net-(CON1A-{slash}REG)") (class "Default")
      (node (ref "CON1") (pin "44") (pinfunction "/REG_44") (pintype "input"))
      (node (ref "R4") (pin "1") (pinfunction "1_1") (pintype "passive"))
    )
    (net (code "70") (name "Net-(CON1A-{slash}WE)") (class "Default")
      (node (ref "CON1") (pin "36") (pinfunction "/WE_36") (pintype "input"))
      (node (ref "R3") (pin "1") (pinfunction "1_1") (pintype "passive"))
    )
    (net (code "71") (name "Net-(IC1A-IR3)") (class "Default")
      (node (ref "IC1") (pin "21") (pinfunction "IR3_21") (pintype "input"))
      (node (ref "IC5") (pin "6") (pinfunction "O_6") (pintype "open_collector"))
      (node (ref "R17") (pin "1") (pinfunction "1_1") (pintype "passive"))
    )
    (net (code "72") (name "Net-(IC1A-SP{slash}EN)") (class "Default")
      (node (ref "IC1") (pin "16") (pinfunction "SP/EN_16") (pintype "bidirectional"))
      (node (ref "R2") (pin "2") (pinfunction "2_2") (pintype "passive"))
    )
    (net (code "73") (name "Net-(IC2A-GATE2)") (class "Default")
      (node (ref "IC2") (pin "16") (pinfunction "GATE2_16") (pintype "input"))
      (node (ref "R11") (pin "1") (pinfunction "1_1") (pintype "passive"))
    )
    (net (code "74") (name "Net-(IC2A-OUT1)") (class "Default")
      (node (ref "IC2") (pin "13") (pinfunction "OUT1_13") (pintype "output"))
      (node (ref "R13") (pin "1") (pinfunction "1_1") (pintype "passive"))
    )
    (net (code "75") (name "Net-(IC3-P26{slash}~{DRQ})") (class "Default")
      (node (ref "IC3") (pin "37") (pinfunction "P26/~{DRQ}_37") (pintype "bidirectional"))
      (node (ref "IC5") (pin "3") (pinfunction "I_3") (pintype "input"))
    )
    (net (code "76") (name "Net-(IC3-P27{slash}~{DAK})") (class "Default")
      (node (ref "IC3") (pin "38") (pinfunction "P27/~{DAK}_38") (pintype "bidirectional"))
      (node (ref "IC5") (pin "1") (pinfunction "I_1") (pintype "input"))
    )
    (net (code "77") (name "Net-(IC3-SS)") (class "Default")
      (node (ref "IC3") (pin "5") (pinfunction "SS_5") (pintype "input"))
      (node (ref "R19") (pin "1") (pinfunction "1_1") (pintype "passive"))
    )
    (net (code "78") (name "Net-(IC3-XTAL1)") (class "Default")
      (node (ref "C9") (pin "2") (pinfunction "2_2") (pintype "passive"))
      (node (ref "IC3") (pin "2") (pinfunction "XTAL1_2") (pintype "input"))
      (node (ref "Q2") (pin "2") (pinfunction "2_2") (pintype "passive"))
    )
    (net (code "79") (name "Net-(IC3-XTAL2)") (class "Default")
      (node (ref "C11") (pin "2") (pinfunction "2_2") (pintype "passive"))
      (node (ref "IC3") (pin "3") (pinfunction "XTAL2_3") (pintype "input"))
      (node (ref "Q2") (pin "1") (pinfunction "1_1") (pintype "passive"))
    )
    (net (code "80") (name "Net-(IC5A-O)") (class "Default")
      (node (ref "IC5") (pin "13") (pinfunction "I_13") (pintype "input"))
      (node (ref "IC5") (pin "2") (pinfunction "O_2") (pintype "open_collector"))
      (node (ref "R9") (pin "2") (pinfunction "2_2") (pintype "passive"))
    )
    (net (code "81") (name "Net-(IC7A-C1+)") (class "Default")
      (node (ref "C4") (pin "2") (pinfunction "2_2") (pintype "passive"))
      (node (ref "IC7") (pin "1") (pinfunction "C1+_1") (pintype "bidirectional"))
    )
    (net (code "82") (name "Net-(IC7A-C1-)") (class "Default")
      (node (ref "C4") (pin "1") (pinfunction "1_1") (pintype "passive"))
      (node (ref "IC7") (pin "3") (pinfunction "C1-_3") (pintype "bidirectional"))
    )
    (net (code "83") (name "Net-(IC7A-C2+)") (class "Default")
      (node (ref "C5") (pin "2") (pinfunction "2_2") (pintype "passive"))
      (node (ref "IC7") (pin "4") (pinfunction "C2+_4") (pintype "bidirectional"))
    )
    (net (code "84") (name "Net-(IC7A-C2-)") (class "Default")
      (node (ref "C5") (pin "1") (pinfunction "1_1") (pintype "passive"))
      (node (ref "IC7") (pin "5") (pinfunction "C2-_5") (pintype "bidirectional"))
    )
    (net (code "85") (name "Net-(IC7A-R1IN)") (class "Default")
      (node (ref "IC7") (pin "13") (pinfunction "R1IN_13") (pintype "input"))
      (node (ref "X1") (pin "2") (pinfunction "2_2") (pintype "passive"))
    )
    (net (code "86") (name "Net-(IC7A-R2IN)") (class "Default")
      (node (ref "IC7") (pin "8") (pinfunction "R2IN_8") (pintype "input"))
      (node (ref "X1") (pin "8") (pinfunction "8_8") (pintype "passive"))
    )
    (net (code "87") (name "Net-(IC7A-T1OUT)") (class "Default")
      (node (ref "IC7") (pin "14") (pinfunction "T1OUT_14") (pintype "output"))
      (node (ref "X1") (pin "3") (pinfunction "3_3") (pintype "passive"))
    )
    (net (code "88") (name "Net-(IC7A-T2OUT)") (class "Default")
      (node (ref "IC7") (pin "7") (pinfunction "T2OUT_7") (pintype "output"))
      (node (ref "X1") (pin "7") (pinfunction "7_7") (pintype "passive"))
    )
    (net (code "89") (name "Net-(IC7A-V+)") (class "Default")
      (node (ref "C6") (pin "1") (pinfunction "1_1") (pintype "passive"))
      (node (ref "IC7") (pin "2") (pinfunction "V+_2") (pintype "bidirectional"))
    )
    (net (code "90") (name "Net-(IC7A-V-)") (class "Default")
      (node (ref "C25") (pin "1") (pinfunction "1_1") (pintype "passive"))
      (node (ref "IC7") (pin "6") (pinfunction "V-_6") (pintype "bidirectional"))
    )
    (net (code "91") (name "Net-(T1-B)") (class "Default")
      (node (ref "R13") (pin "2") (pinfunction "2_2") (pintype "passive"))
      (node (ref "T1") (pin "1") (pinfunction "B_1") (pintype "passive"))
    )
    (net (code "92") (name "Net-(T1-C)") (class "Default")
      (node (ref "R15") (pin "1") (pinfunction "1_1") (pintype "passive"))
      (node (ref "T1") (pin "3") (pinfunction "C_3") (pintype "passive"))
    )
    (net (code "93") (name "Net-(U$1-READY)") (class "Default")
      (node (ref "R12") (pin "1") (pinfunction "1_1") (pintype "passive"))
      (node (ref "U$1") (pin "6") (pinfunction "READY_6") (pintype "bidirectional"))
    )
    (net (code "94") (name "Net-(U$2-XT)") (class "Default")
      (node (ref "C23") (pin "2") (pinfunction "2_2") (pintype "passive"))
      (node (ref "U$2") (pin "16") (pinfunction "XT_16") (pintype "bidirectional"))
      (node (ref "X2") (pin "2") (pinfunction "2_2") (pintype "passive"))
    )
    (net (code "95") (name "Net-(U$2-~{XT})") (class "Default")
      (node (ref "C20") (pin "2") (pinfunction "2_2") (pintype "passive"))
      (node (ref "U$2") (pin "17") (pinfunction "~{XT}_17") (pintype "bidirectional"))
      (node (ref "X2") (pin "1") (pinfunction "1_1") (pintype "passive"))
    )
    (net (code "96") (name "Net-(U$5-~{CLR})") (class "Default")
      (node (ref "R1") (pin "2") (pinfunction "2_2") (pintype "passive"))
      (node (ref "U$5") (pin "14") (pinfunction "~{CLR}_14") (pintype "bidirectional"))
    )
    (net (code "97") (name "OUT_1") (class "Default")
      (node (ref "SV2") (pin "3") (pinfunction "3_3") (pintype "passive"))
    )
    (net (code "98") (name "OUT_2") (class "Default")
      (node (ref "SV2") (pin "4") (pinfunction "4_4") (pintype "passive"))
    )
    (net (code "99") (name "OUT_3") (class "Default")
      (node (ref "SV2") (pin "5") (pinfunction "5_5") (pintype "passive"))
    )
    (net (code "100") (name "OUT_4") (class "Default")
      (node (ref "SV2") (pin "6") (pinfunction "6_6") (pintype "passive"))
    )
    (net (code "101") (name "RD") (class "Default")
      (node (ref "IC3") (pin "8") (pinfunction "RD_8") (pintype "input"))
      (node (ref "SV2") (pin "39") (pinfunction "39_39") (pintype "passive"))
      (node (ref "U$1") (pin "3") (pinfunction "~{MEMR}_3") (pintype "bidirectional"))
    )
    (net (code "102") (name "READY") (class "Default")
      (node (ref "SV2") (pin "1") (pinfunction "1_1") (pintype "passive"))
    )
    (net (code "103") (name "RESET") (class "Default")
      (node (ref "IC6") (pin "21") (pinfunction "RESET_21") (pintype "input"))
      (node (ref "SV2") (pin "31") (pinfunction "31_31") (pintype "passive"))
      (node (ref "U$1") (pin "13") (pinfunction "RESET_13") (pintype "bidirectional"))
    )
    (net (code "104") (name "RTC_IRQ") (class "Default")
      (node (ref "IC5") (pin "5") (pinfunction "I_5") (pintype "input"))
      (node (ref "R10") (pin "2") (pinfunction "2_2") (pintype "passive"))
      (node (ref "U$2") (pin "1") (pinfunction "STD.P_1") (pintype "bidirectional"))
    )
    (net (code "105") (name "RTS") (class "Default")
      (node (ref "IC6") (pin "23") (pinfunction "~{RTS}_23") (pintype "output"))
      (node (ref "IC7") (pin "10") (pinfunction "T2IN_10") (pintype "input"))
    )
    (net (code "106") (name "RXD_TTL") (class "Default")
      (node (ref "IC6") (pin "3") (pinfunction "RXD_3") (pintype "input"))
      (node (ref "IC7") (pin "12") (pinfunction "R1OUT_12") (pintype "output"))
    )
    (net (code "107") (name "TC_8257") (class "Default")
      (node (ref "SV2") (pin "54") (pinfunction "54_54") (pintype "passive"))
      (node (ref "U$1") (pin "36") (pinfunction "TC_36") (pintype "bidirectional"))
    )
    (net (code "108") (name "TIMER_CS") (class "Default")
      (node (ref "IC2") (pin "21") (pinfunction "CS_21") (pintype "input"))
      (node (ref "IC4") (pin "11") (pinfunction "Y1_11") (pintype "output"))
    )
    (net (code "109") (name "TIMER_IRQ") (class "Default")
      (node (ref "IC1") (pin "22") (pinfunction "IR4_22") (pintype "input"))
      (node (ref "IC2") (pin "10") (pinfunction "OUT0_10") (pintype "output"))
    )
    (net (code "110") (name "TXD") (class "Default")
      (node (ref "IC6") (pin "19") (pinfunction "TXD_19") (pintype "output"))
      (node (ref "IC7") (pin "11") (pinfunction "T1IN_11") (pintype "input"))
    )
    (net (code "111") (name "UART_BAUD") (class "Default")
      (node (ref "IC2") (pin "17") (pinfunction "OUT2_17") (pintype "output"))
      (node (ref "IC6") (pin "25") (pinfunction "~{RXC}_25") (pintype "input"))
      (node (ref "IC6") (pin "9") (pinfunction "~{TXC}_9") (pintype "input"))
    )
    (net (code "112") (name "UART_CS") (class "Default")
      (node (ref "IC4") (pin "12") (pinfunction "Y0_12") (pintype "output"))
      (node (ref "IC6") (pin "11") (pinfunction "~{CS}_11") (pintype "input"))
    )
    (net (code "113") (name "UART_RX_IRQ") (class "Default")
      (node (ref "IC1") (pin "20") (pinfunction "IR2_20") (pintype "input"))
      (node (ref "IC6") (pin "14") (pinfunction "RXRDY_14") (pintype "output"))
    )
    (net (code "114") (name "UART_TX_IRQ") (class "Default")
      (node (ref "IC1") (pin "19") (pinfunction "IR1_19") (pintype "input"))
      (node (ref "IC6") (pin "15") (pinfunction "TXRDY_15") (pintype "output"))
    )
    (net (code "115") (name "VCC") (class "Default")
      (node (ref "C1") (pin "1") (pinfunction "1_1") (pintype "passive"))
      (node (ref "C10") (pin "1") (pinfunction "1_1") (pintype "passive"))
      (node (ref "C12") (pin "1") (pinfunction "1_1") (pintype "passive"))
      (node (ref "C14") (pin "1") (pinfunction "1_1") (pintype "passive"))
      (node (ref "C15") (pin "1") (pinfunction "1_1") (pintype "passive"))
      (node (ref "C16") (pin "1") (pinfunction "1_1") (pintype "passive"))
      (node (ref "C17") (pin "1") (pinfunction "1_1") (pintype "passive"))
      (node (ref "C19") (pin "1") (pinfunction "1_1") (pintype "passive"))
      (node (ref "C2") (pin "1") (pinfunction "1_1") (pintype "passive"))
      (node (ref "C21") (pin "+") (pinfunction "+_+") (pintype "passive"))
      (node (ref "C24") (pin "+") (pinfunction "+_+") (pintype "passive"))
      (node (ref "C3") (pin "1") (pinfunction "1_1") (pintype "passive"))
      (node (ref "C6") (pin "2") (pinfunction "2_2") (pintype "passive"))
      (node (ref "CON1") (pin "13") (pinfunction "VCC2_13") (pintype "power_in"))
      (node (ref "CON1") (pin "38") (pinfunction "VCC1_38") (pintype "power_in"))
      (node (ref "D2") (pin "A") (pinfunction "A_A") (pintype "passive"))
      (node (ref "IC1") (pin "28") (pinfunction "VCC_28") (pintype "power_in"))
      (node (ref "IC2") (pin "24") (pinfunction "VCC_24") (pintype "power_in"))
      (node (ref "IC3") (pin "25") (pinfunction "PROG_25") (pintype "bidirectional"))
      (node (ref "IC3") (pin "26") (pinfunction "VDD_26") (pintype "power_in"))
      (node (ref "IC3") (pin "40") (pinfunction "VCC_40") (pintype "power_in"))
      (node (ref "IC4") (pin "16") (pinfunction "VCC_16") (pintype "power_in"))
      (node (ref "IC5") (pin "14") (pinfunction "VCC_14") (pintype "power_in"))
      (node (ref "IC6") (pin "26") (pinfunction "VCC_26") (pintype "power_in"))
      (node (ref "IC7") (pin "16") (pinfunction "VCC_16") (pintype "power_in"))
      (node (ref "J1") (pin "5") (pinfunction "5_5") (pintype "bidirectional"))
      (node (ref "JP3") (pin "1") (pinfunction "1_1") (pintype "passive"))
      (node (ref "R1") (pin "1") (pinfunction "1_1") (pintype "passive"))
      (node (ref "R10") (pin "1") (pinfunction "1_1") (pintype "passive"))
      (node (ref "R11") (pin "2") (pinfunction "2_2") (pintype "passive"))
      (node (ref "R12") (pin "2") (pinfunction "2_2") (pintype "passive"))
      (node (ref "R14") (pin "2") (pinfunction "2_2") (pintype "passive"))
      (node (ref "R17") (pin "2") (pinfunction "2_2") (pintype "passive"))
      (node (ref "R19") (pin "2") (pinfunction "2_2") (pintype "passive"))
      (node (ref "R2") (pin "1") (pinfunction "1_1") (pintype "passive"))
      (node (ref "R3") (pin "2") (pinfunction "2_2") (pintype "passive"))
      (node (ref "R4") (pin "2") (pinfunction "2_2") (pintype "passive"))
      (node (ref "R5") (pin "2") (pinfunction "2_2") (pintype "passive"))
      (node (ref "R6") (pin "2") (pinfunction "2_2") (pintype "passive"))
      (node (ref "R7") (pin "2") (pinfunction "2_2") (pintype "passive"))
      (node (ref "R8") (pin "2") (pinfunction "2_2") (pintype "passive"))
      (node (ref "R9") (pin "1") (pinfunction "1_1") (pintype "passive"))
      (node (ref "U$1") (pin "31") (pinfunction "VCC_31") (pintype "bidirectional"))
      (node (ref "U$2") (pin "15") (pinfunction "CS1_15") (pintype "bidirectional"))
      (node (ref "U$2") (pin "3") (pinfunction "ALE_3") (pintype "bidirectional"))
      (node (ref "U$5") (pin "24") (pinfunction "VCC_24") (pintype "bidirectional"))
    )
    (net (code "116") (name "VPA") (class "Default")
      (node (ref "C13") (pin "2") (pinfunction "2_2") (pintype "passive"))
      (node (ref "C18") (pin "+") (pinfunction "+_+") (pintype "passive"))
      (node (ref "D1") (pin "C") (pinfunction "C_C") (pintype "passive"))
      (node (ref "D2") (pin "C") (pinfunction "C_C") (pintype "passive"))
      (node (ref "U$2") (pin "18") (pinfunction "VDD_18") (pintype "bidirectional"))
    )
    (net (code "117") (name "WR") (class "Default")
      (node (ref "IC3") (pin "10") (pinfunction "WR_10") (pintype "input"))
      (node (ref "SV2") (pin "40") (pinfunction "40_40") (pintype "passive"))
      (node (ref "U$1") (pin "4") (pinfunction "~{MEMW}_4") (pintype "bidirectional"))
    )
    (net (code "118") (name "unconnected-(CON1A-D08-Pad47)") (class "Default")
      (node (ref "CON1") (pin "47") (pinfunction "D08_47") (pintype "bidirectional"))
    )
    (net (code "119") (name "unconnected-(CON1A-D09-Pad48)") (class "Default")
      (node (ref "CON1") (pin "48") (pinfunction "D09_48") (pintype "bidirectional"))
    )
    (net (code "120") (name "unconnected-(CON1A-D10-Pad49)") (class "Default")
      (node (ref "CON1") (pin "49") (pinfunction "D10_49") (pintype "bidirectional"))
    )
    (net (code "121") (name "unconnected-(CON1A-D11-Pad27)") (class "Default")
      (node (ref "CON1") (pin "27") (pinfunction "D11_27") (pintype "bidirectional"))
    )
    (net (code "122") (name "unconnected-(CON1A-D12-Pad28)") (class "Default")
      (node (ref "CON1") (pin "28") (pinfunction "D12_28") (pintype "bidirectional"))
    )
    (net (code "123") (name "unconnected-(CON1A-D13-Pad29)") (class "Default")
      (node (ref "CON1") (pin "29") (pinfunction "D13_29") (pintype "bidirectional"))
    )
    (net (code "124") (name "unconnected-(CON1A-D14-Pad30)") (class "Default")
      (node (ref "CON1") (pin "30") (pinfunction "D14_30") (pintype "bidirectional"))
    )
    (net (code "125") (name "unconnected-(CON1A-D15-Pad31)") (class "Default")
      (node (ref "CON1") (pin "31") (pinfunction "D15_31") (pintype "bidirectional"))
    )
    (net (code "126") (name "unconnected-(CON1A-INTRQ-Pad37)") (class "Default")
      (node (ref "CON1") (pin "37") (pinfunction "INTRQ_37") (pintype "output"))
    )
    (net (code "127") (name "unconnected-(CON1A-IORDY-Pad42)") (class "Default")
      (node (ref "CON1") (pin "42") (pinfunction "IORDY_42") (pintype "output"))
    )
    (net (code "128") (name "unconnected-(CON1A-{slash}CD1-Pad26)") (class "Default")
      (node (ref "CON1") (pin "26") (pinfunction "/CD1_26") (pintype "output"))
    )
    (net (code "129") (name "unconnected-(CON1A-{slash}CD2-Pad25)") (class "Default")
      (node (ref "CON1") (pin "25") (pinfunction "/CD2_25") (pintype "output"))
    )
    (net (code "130") (name "unconnected-(CON1A-{slash}DASP-Pad45)") (class "Default")
      (node (ref "CON1") (pin "45") (pinfunction "/DASP_45") (pintype "bidirectional"))
    )
    (net (code "131") (name "unconnected-(CON1A-{slash}INPACK-Pad43)") (class "Default")
      (node (ref "CON1") (pin "43") (pinfunction "/INPACK_43") (pintype "output"))
    )
    (net (code "132") (name "unconnected-(CON1A-{slash}IOCS16-Pad24)") (class "Default")
      (node (ref "CON1") (pin "24") (pinfunction "/IOCS16_24") (pintype "output"))
    )
    (net (code "133") (name "unconnected-(CON1A-{slash}VS1-Pad33)") (class "Default")
      (node (ref "CON1") (pin "33") (pinfunction "/VS1_33") (pintype "output"))
    )
    (net (code "134") (name "unconnected-(CON1A-{slash}VS2-Pad40)") (class "Default")
      (node (ref "CON1") (pin "40") (pinfunction "/VS2_40") (pintype "output"))
    )
    (net (code "135") (name "unconnected-(IC1A-CAS0-Pad12)") (class "Default")
      (node (ref "IC1") (pin "12") (pinfunction "CAS0_12") (pintype "bidirectional"))
    )
    (net (code "136") (name "unconnected-(IC1A-CAS1-Pad13)") (class "Default")
      (node (ref "IC1") (pin "13") (pinfunction "CAS1_13") (pintype "bidirectional"))
    )
    (net (code "137") (name "unconnected-(IC1A-CAS2-Pad15)") (class "Default")
      (node (ref "IC1") (pin "15") (pinfunction "CAS2_15") (pintype "bidirectional"))
    )
    (net (code "138") (name "unconnected-(IC3-P10-Pad27)") (class "Default")
      (node (ref "IC3") (pin "27") (pinfunction "P10_27") (pintype "bidirectional"))
    )
    (net (code "139") (name "unconnected-(IC3-P11-Pad28)") (class "Default")
      (node (ref "IC3") (pin "28") (pinfunction "P11_28") (pintype "bidirectional"))
    )
    (net (code "140") (name "unconnected-(IC3-P12-Pad29)") (class "Default")
      (node (ref "IC3") (pin "29") (pinfunction "P12_29") (pintype "bidirectional"))
    )
    (net (code "141") (name "unconnected-(IC3-P13-Pad30)") (class "Default")
      (node (ref "IC3") (pin "30") (pinfunction "P13_30") (pintype "bidirectional"))
    )
    (net (code "142") (name "unconnected-(IC3-P14-Pad31)") (class "Default")
      (node (ref "IC3") (pin "31") (pinfunction "P14_31") (pintype "bidirectional"))
    )
    (net (code "143") (name "unconnected-(IC3-P15-Pad32)") (class "Default")
      (node (ref "IC3") (pin "32") (pinfunction "P15_32") (pintype "bidirectional"))
    )
    (net (code "144") (name "unconnected-(IC3-P16-Pad33)") (class "Default")
      (node (ref "IC3") (pin "33") (pinfunction "P16_33") (pintype "bidirectional"))
    )
    (net (code "145") (name "unconnected-(IC3-P17-Pad34)") (class "Default")
      (node (ref "IC3") (pin "34") (pinfunction "P17_34") (pintype "bidirectional"))
    )
    (net (code "146") (name "unconnected-(IC3-P20-Pad21)") (class "Default")
      (node (ref "IC3") (pin "21") (pinfunction "P20_21") (pintype "bidirectional"))
    )
    (net (code "147") (name "unconnected-(IC3-P21-Pad22)") (class "Default")
      (node (ref "IC3") (pin "22") (pinfunction "P21_22") (pintype "bidirectional"))
    )
    (net (code "148") (name "unconnected-(IC3-P25{slash}~{IBF}-Pad36)") (class "Default")
      (node (ref "IC3") (pin "36") (pinfunction "P25/~{IBF}_36") (pintype "bidirectional"))
    )
    (net (code "149") (name "unconnected-(IC3-SYNC-Pad11)") (class "Default")
      (node (ref "IC3") (pin "11") (pinfunction "SYNC_11") (pintype "output"))
    )
    (net (code "150") (name "unconnected-(IC4A-Y2-Pad6)") (class "Default")
      (node (ref "IC4") (pin "6") (pinfunction "Y2_6") (pintype "output"))
    )
    (net (code "151") (name "unconnected-(IC4A-Y3-Pad7)") (class "Default")
      (node (ref "IC4") (pin "7") (pinfunction "Y3_7") (pintype "output"))
    )
    (net (code "152") (name "unconnected-(IC5D-O-Pad8)") (class "Default")
      (node (ref "IC5") (pin "8") (pinfunction "O_8") (pintype "open_collector"))
    )
    (net (code "153") (name "unconnected-(IC5E-O-Pad10)") (class "Default")
      (node (ref "IC5") (pin "10") (pinfunction "O_10") (pintype "open_collector"))
    )
    (net (code "154") (name "unconnected-(IC6-SYNDET-Pad16)") (class "Default")
      (node (ref "IC6") (pin "16") (pinfunction "SYNDET_16") (pintype "bidirectional"))
    )
    (net (code "155") (name "unconnected-(IC6-TXE-Pad18)") (class "Default")
      (node (ref "IC6") (pin "18") (pinfunction "TXE_18") (pintype "output"))
    )
    (net (code "156") (name "unconnected-(IC6-~{DTR}-Pad24)") (class "Default")
      (node (ref "IC6") (pin "24") (pinfunction "~{DTR}_24") (pintype "output"))
    )
    (net (code "157") (name "unconnected-(J1-Pad3)") (class "Default")
      (node (ref "J1") (pin "3") (pinfunction "3_3") (pintype "bidirectional"))
    )
    (net (code "158") (name "unconnected-(SV2-Pad53)") (class "Default")
      (node (ref "SV2") (pin "53") (pinfunction "53_53") (pintype "passive"))
    )
    (net (code "159") (name "unconnected-(SV2-Pad55)") (class "Default")
      (node (ref "SV2") (pin "55") (pinfunction "55_55") (pintype "passive"))
    )
    (net (code "160") (name "unconnected-(SV2-Pad56)") (class "Default")
      (node (ref "SV2") (pin "56") (pinfunction "56_56") (pintype "passive"))
    )
    (net (code "161") (name "unconnected-(SV2-Pad64)") (class "Default")
      (node (ref "SV2") (pin "64") (pinfunction "64_64") (pintype "passive"))
    )
    (net (code "162") (name "unconnected-(U$1-MARK-Pad5)") (class "Default")
      (node (ref "U$1") (pin "5") (pinfunction "MARK_5") (pintype "bidirectional"))
    )
    (net (code "163") (name "unconnected-(U$5-~{INT}-Pad23)") (class "Default")
      (node (ref "U$5") (pin "23") (pinfunction "~{INT}_23") (pintype "bidirectional"))
    )
    (net (code "164") (name "unconnected-(X1-Pad1)") (class "Default")
      (node (ref "X1") (pin "1") (pinfunction "1_1") (pintype "passive"))
    )
    (net (code "165") (name "unconnected-(X1-Pad4)") (class "Default")
      (node (ref "X1") (pin "4") (pinfunction "4_4") (pintype "passive"))
    )
    (net (code "166") (name "unconnected-(X1-Pad6)") (class "Default")
      (node (ref "X1") (pin "6") (pinfunction "6_6") (pintype "passive"))
    )
    (net (code "167") (name "unconnected-(X1-Pad9)") (class "Default")
      (node (ref "X1") (pin "9") (pinfunction "9_9") (pintype "passive"))
    )
  )
)
